# EagleIO_copy.net
KiCad netlist of a schematic drawn in EAGLE
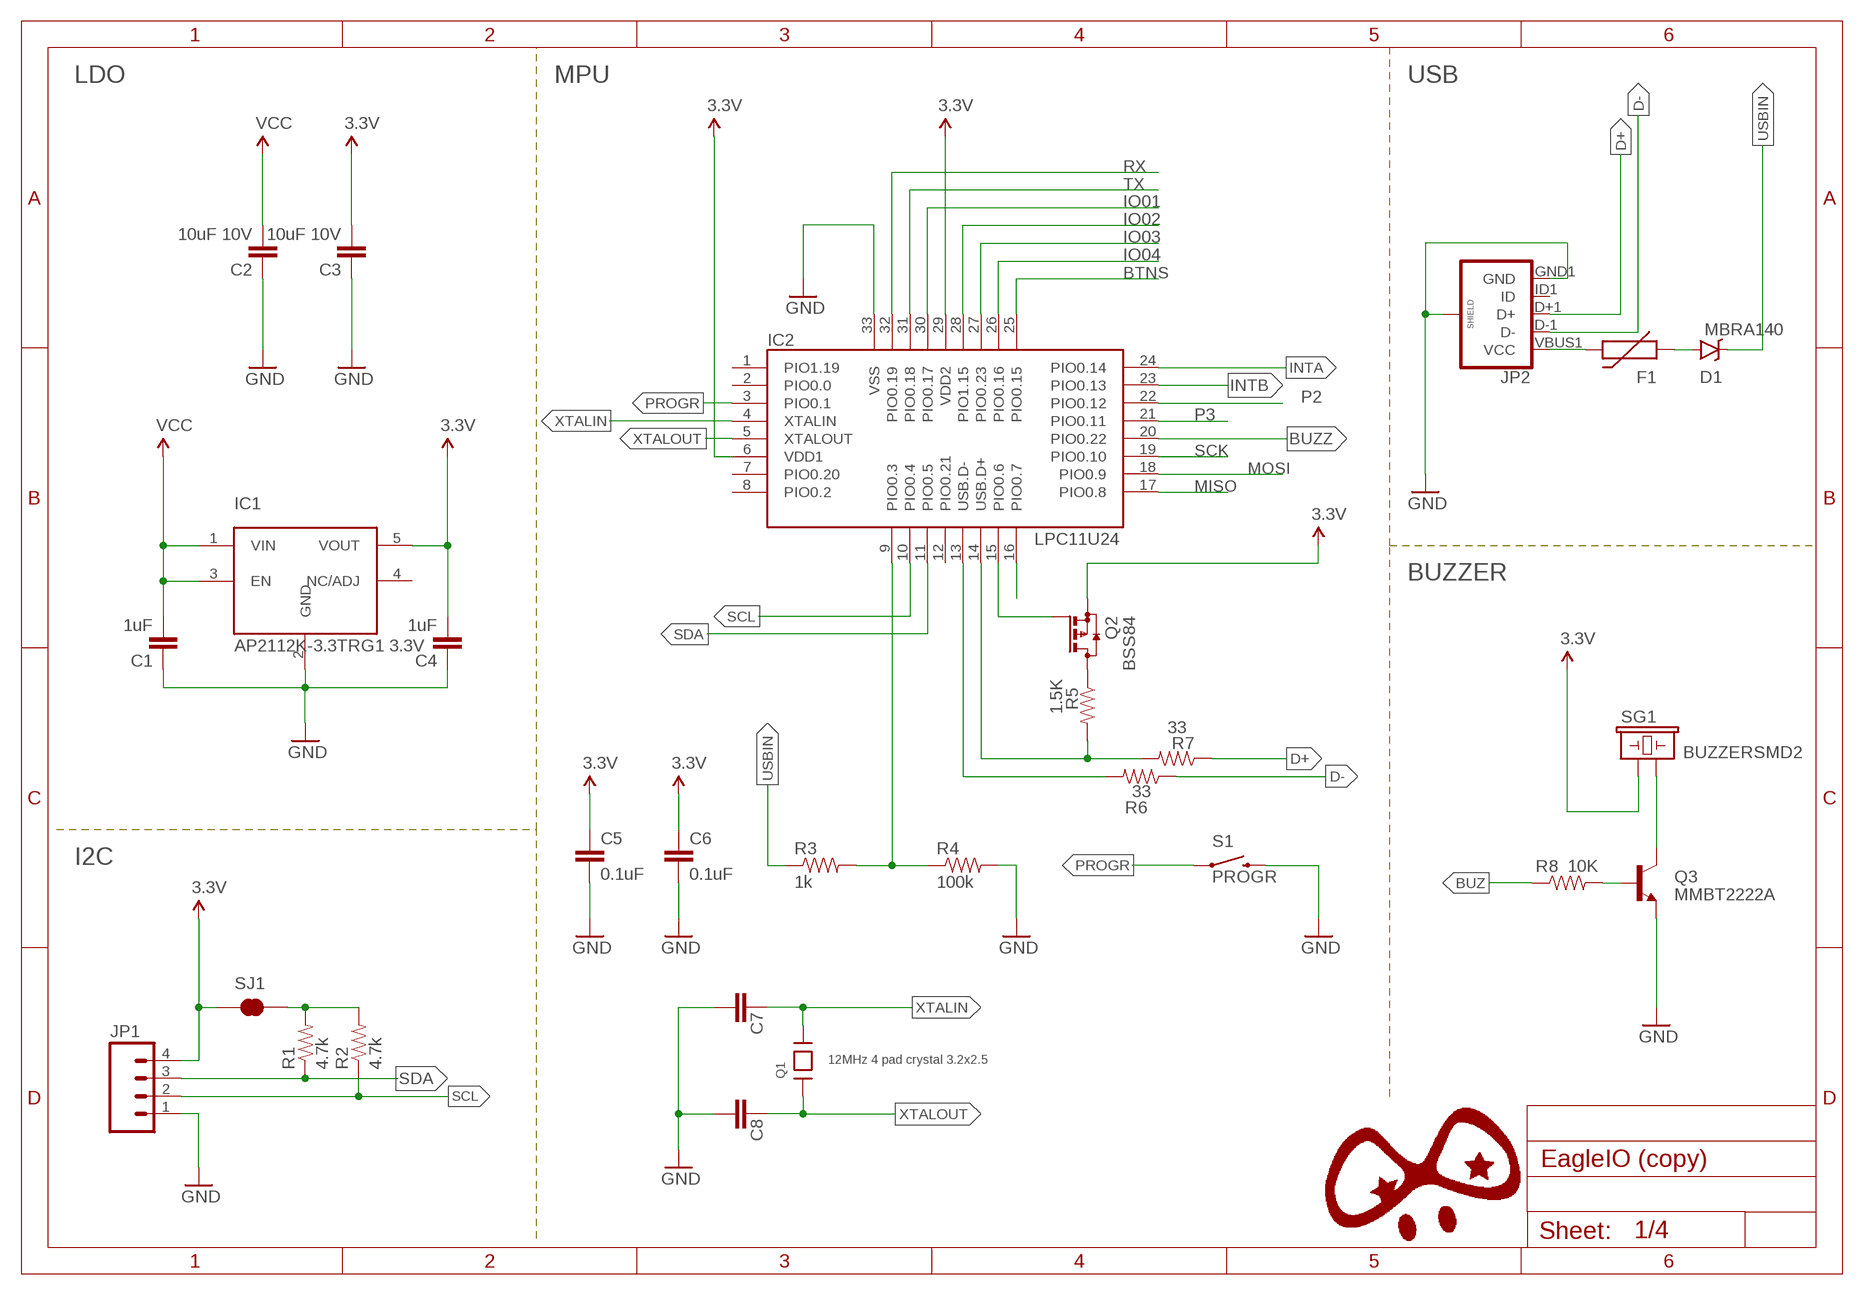
[diagram p0: schematic, sheet 1]
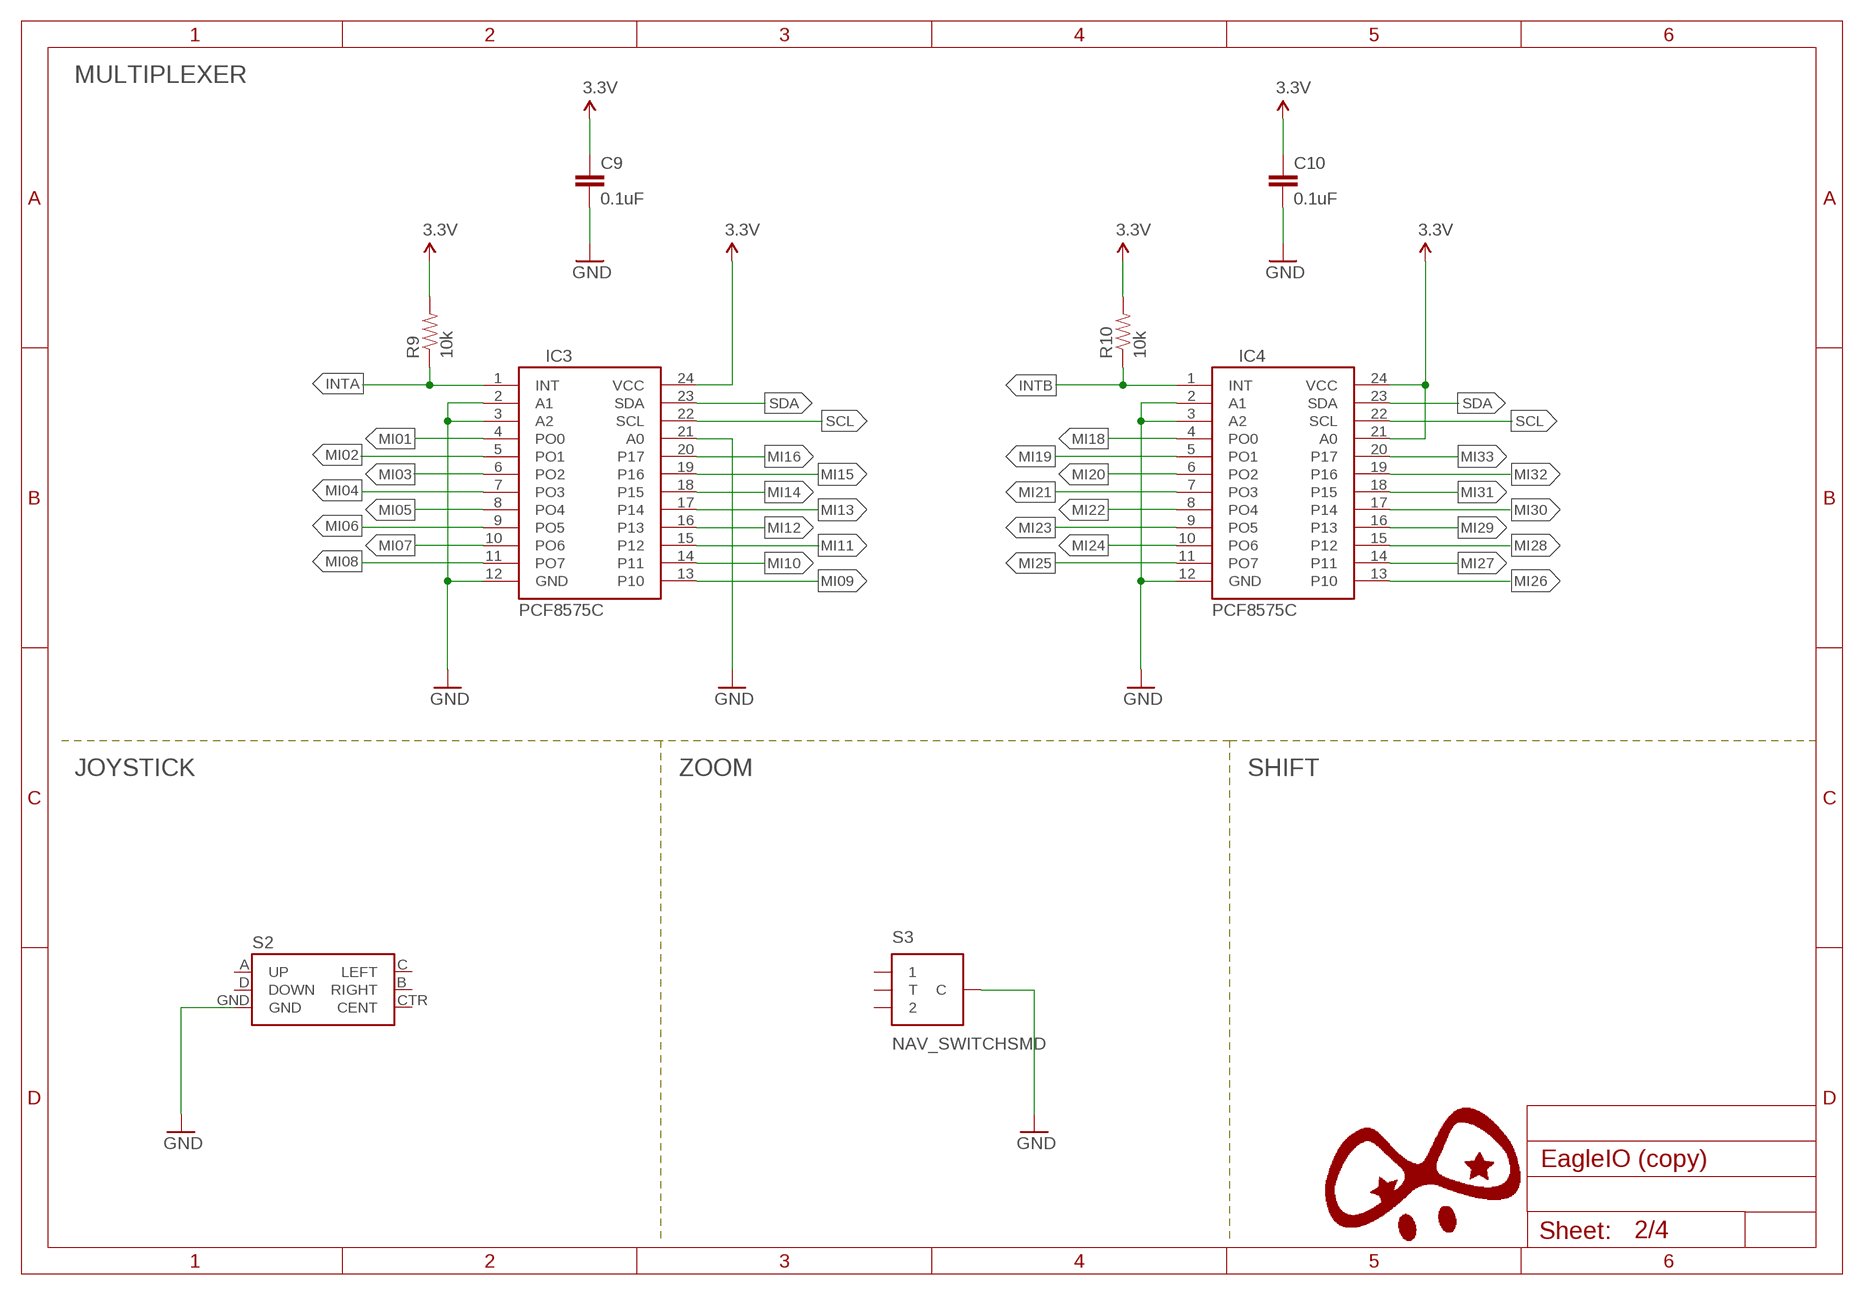
[diagram p1: schematic, sheet 2]
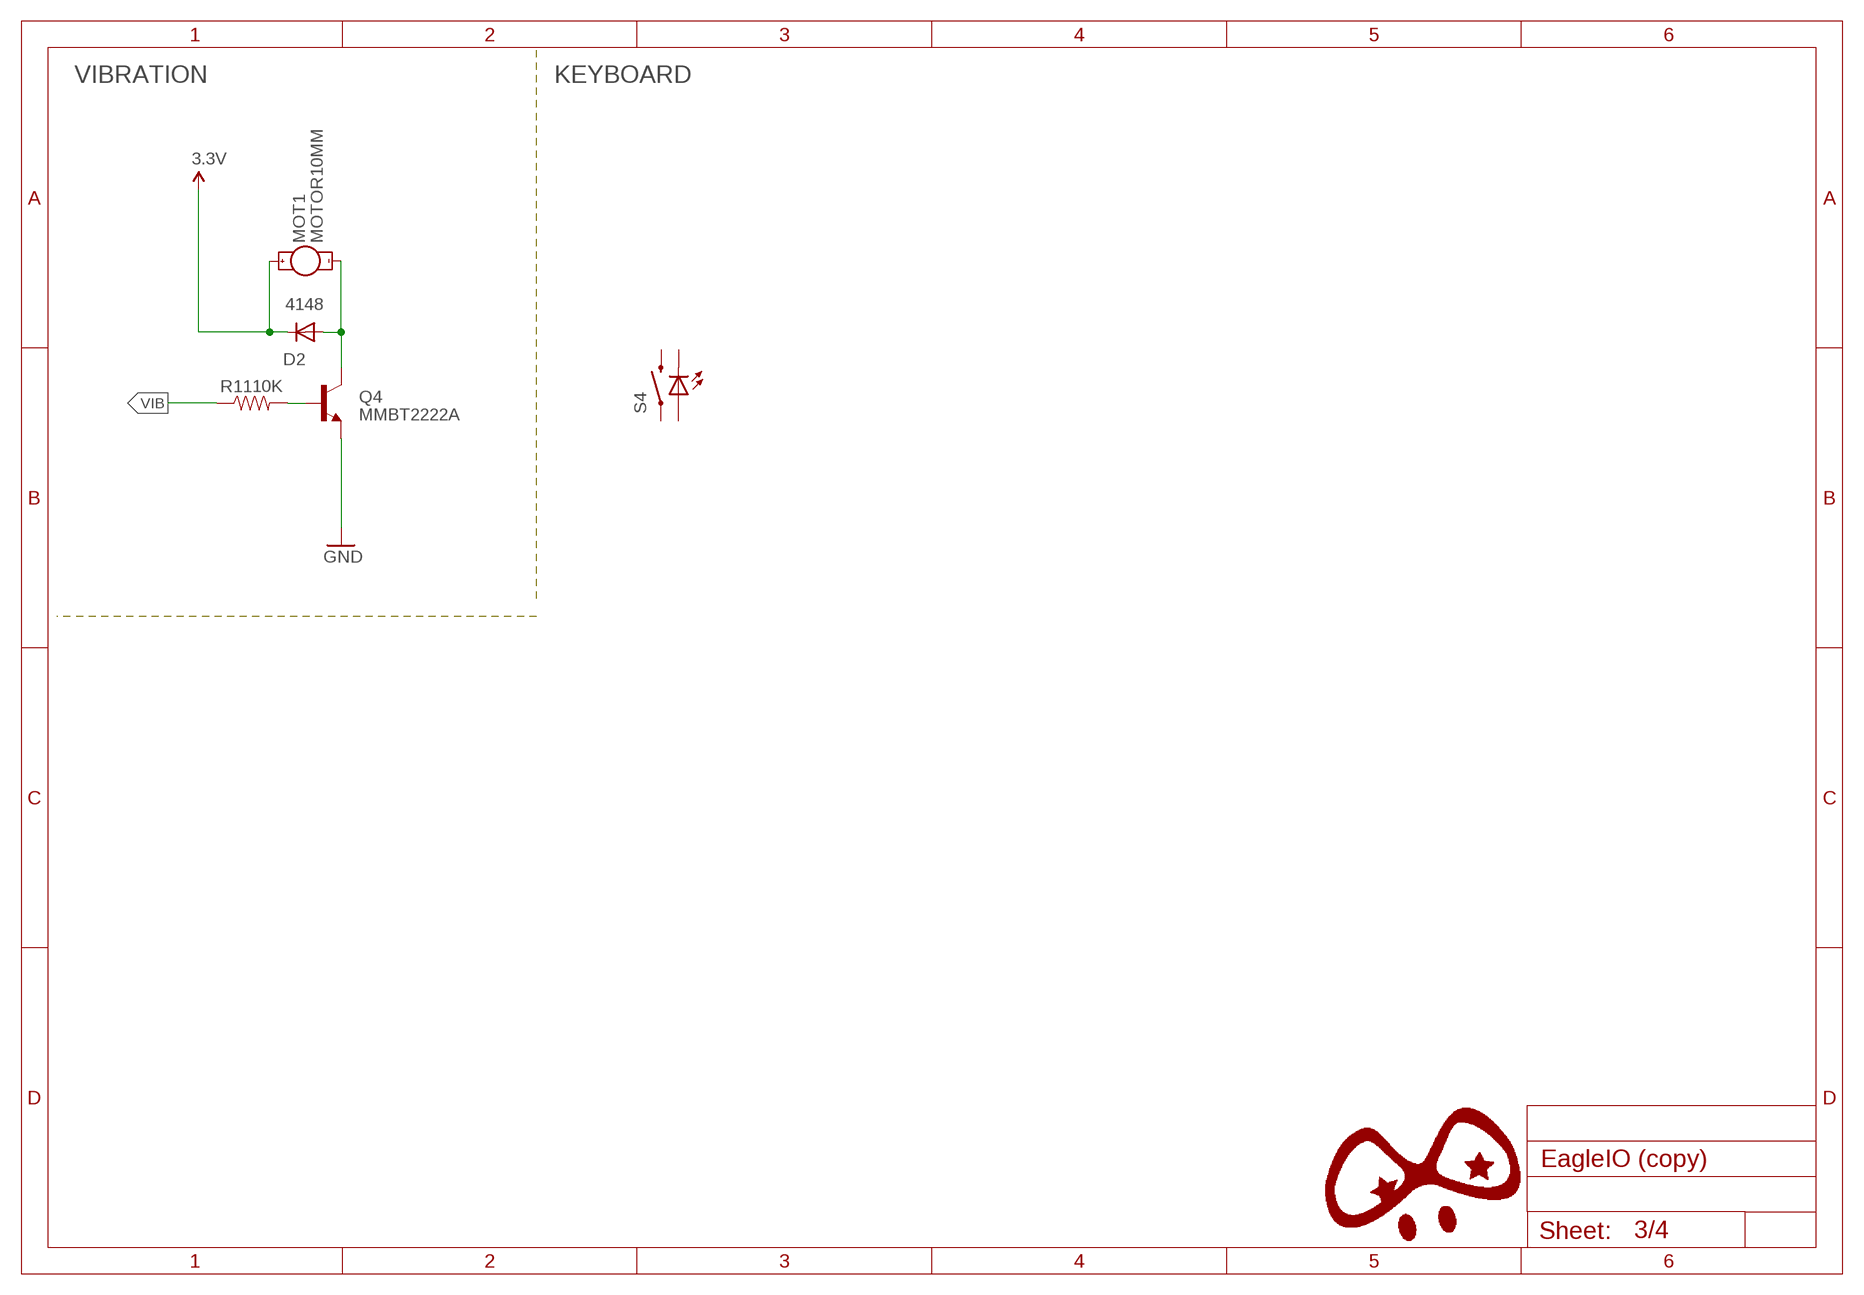
[diagram p2: schematic, sheet 3]
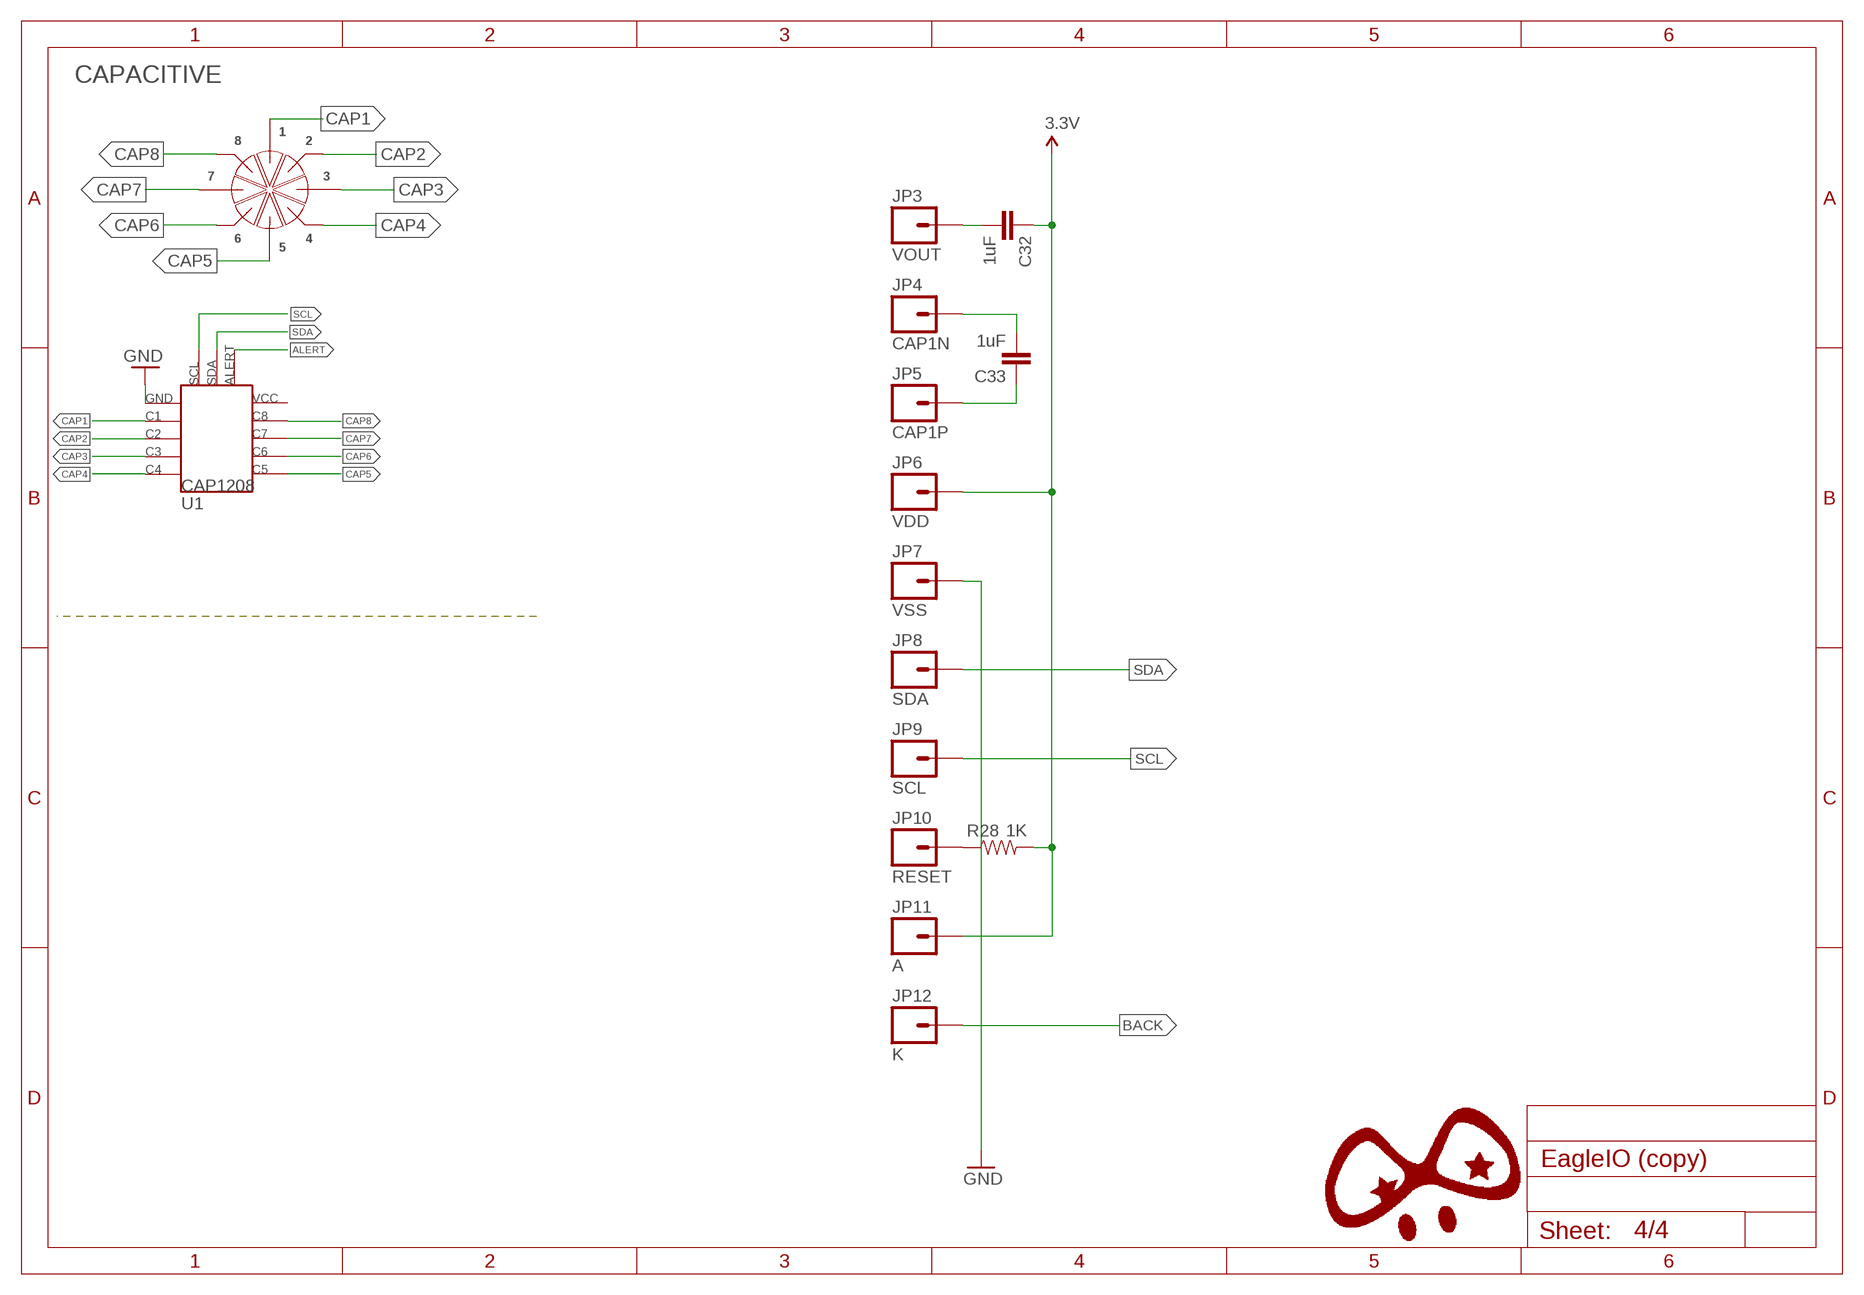
[diagram p3: schematic, sheet 4]

(export (version "E")
  (design (tool "Eeschema 10.0.6"))
  (components
    (comp (ref "C9")
      (value "0.1uF")
      (footprint "eagle-import:0402-CAP")
      (libsource (lib "eagle-import") (part "CAP0402-CAP"))
    )
    (comp (ref "C10")
      (value "0.1uF")
      (footprint "eagle-import:0402-CAP")
      (libsource (lib "eagle-import") (part "CAP0402-CAP"))
    )
    (comp (ref "IC3")
      (value "PCF8575C")
      (footprint "eagle-import:SO-24DW")
      (libsource (lib "eagle-import") (part "PCF8575C"))
    )
    (comp (ref "IC4")
      (value "PCF8575C")
      (footprint "eagle-import:SO-24DW")
      (libsource (lib "eagle-import") (part "PCF8575C"))
    )
    (comp (ref "R9")
      (value "10k")
      (footprint "eagle-import:0402-RES")
      (libsource (lib "eagle-import") (part "SparkFun-Passives_RESISTOR0402-RES"))
    )
    (comp (ref "R10")
      (value "10k")
      (footprint "eagle-import:0402-RES")
      (libsource (lib "eagle-import") (part "SparkFun-Passives_RESISTOR0402-RES"))
    )
    (comp (ref "S2")
      (value "JOYSTICK_MINI")
      (footprint "eagle-import:JOYSTICK_MINI")
      (libsource (lib "eagle-import") (part "JOYSTICK_MINI"))
    )
    (comp (ref "S3")
      (value "NAV_SWITCHSMD")
      (footprint "eagle-import:NAV_SWITCH")
      (libsource (lib "eagle-import") (part "NAV_SWITCHSMD"))
    )
    (comp (ref "C1")
      (value "1uF")
      (footprint "eagle-import:0402-CAP")
      (libsource (lib "eagle-import") (part "CAP0402-CAP"))
    )
    (comp (ref "C2")
      (value "10uF 10V")
      (footprint "eagle-import:0402-CAP")
      (libsource (lib "eagle-import") (part "CAP0402-CAP"))
    )
    (comp (ref "C3")
      (value "10uF 10V")
      (footprint "eagle-import:0402-CAP")
      (libsource (lib "eagle-import") (part "CAP0402-CAP"))
    )
    (comp (ref "C4")
      (value "1uF")
      (footprint "eagle-import:0402-CAP")
      (libsource (lib "eagle-import") (part "CAP0402-CAP"))
    )
    (comp (ref "C5")
      (value "0.1uF")
      (footprint "eagle-import:0402-CAP")
      (libsource (lib "eagle-import") (part "CAP0402-CAP"))
    )
    (comp (ref "C6")
      (value "0.1uF")
      (footprint "eagle-import:0402-CAP")
      (libsource (lib "eagle-import") (part "CAP0402-CAP"))
    )
    (comp (ref "C7")
      (value "27pF")
      (footprint "eagle-import:0402-CAP")
      (libsource (lib "eagle-import") (part "CAP0402-CAP"))
    )
    (comp (ref "C8")
      (value "27pF")
      (footprint "eagle-import:0402-CAP")
      (libsource (lib "eagle-import") (part "CAP0402-CAP"))
    )
    (comp (ref "D1")
      (value "MBRA140")
      (footprint "eagle-import:SMA-DIODE")
      (libsource (lib "eagle-import") (part "MBRA140"))
    )
    (comp (ref "F1")
      (value "PTC0603")
      (footprint "eagle-import:0603")
      (libsource (lib "eagle-import") (part "PTC0603"))
    )
    (comp (ref "IC1")
      (value "AP2112K-3.3TRG1 3.3V")
      (footprint "eagle-import:SOT23-5")
      (libsource (lib "eagle-import") (part "5PIN_REG"))
    )
    (comp (ref "IC2")
      (value "LPC11U24")
      (footprint "eagle-import:HVQFN33_5X5MM")
      (libsource (lib "eagle-import") (part "LPC11U2X_HVQFN33(5X5)"))
    )
    (comp (ref "JP1")
      (value "M04LONGPADS")
      (footprint "eagle-import:1X04_LONGPADS")
      (libsource (lib "eagle-import") (part "M04LONGPADS"))
    )
    (comp (ref "JP2")
      (value "USB_MICROB_PLUGCONN-11752")
      (footprint "eagle-import:USB-B-MICRO-SMD_V03")
      (libsource (lib "eagle-import") (part "USB_MICROB_PLUGCONN-11752"))
    )
    (comp (ref "Q1")
      (value "12MHz 4 pad crystal 3.2x2.5")
      (footprint "eagle-import:CRYSTAL_3.2X2.5")
      (libsource (lib "eagle-import") (part "CRYSTAL3.2X2.5"))
    )
    (comp (ref "Q2")
      (value "BSS84")
      (footprint "eagle-import:SOT23")
      (libsource (lib "eagle-import") (part "BSS84"))
    )
    (comp (ref "Q3")
      (value "MMBT2222A")
      (footprint "eagle-import:SOT23-3")
      (libsource (lib "eagle-import") (part "TRANSISTOR_NPNMMBT2222A"))
    )
    (comp (ref "R1")
      (value "4.7k")
      (footprint "eagle-import:0402-RES")
      (libsource (lib "eagle-import") (part "SparkFun-Passives_RESISTOR0402-RES"))
    )
    (comp (ref "R2")
      (value "4.7k")
      (footprint "eagle-import:0402-RES")
      (libsource (lib "eagle-import") (part "SparkFun-Passives_RESISTOR0402-RES"))
    )
    (comp (ref "R3")
      (value "1k")
      (footprint "eagle-import:0402-RES")
      (libsource (lib "eagle-import") (part "SparkFun-Passives_RESISTOR0402-RES"))
    )
    (comp (ref "R4")
      (value "100k")
      (footprint "eagle-import:0402-RES")
      (libsource (lib "eagle-import") (part "SparkFun-Passives_RESISTOR0402-RES"))
    )
    (comp (ref "R5")
      (value "1.5K")
      (footprint "eagle-import:0402-RES")
      (libsource (lib "eagle-import") (part "SparkFun-Passives_RESISTOR0402-RES"))
    )
    (comp (ref "R6")
      (value "33")
      (footprint "eagle-import:0402-RES")
      (libsource (lib "eagle-import") (part "SparkFun-Passives_RESISTOR0402-RES"))
    )
    (comp (ref "R7")
      (value "33")
      (footprint "eagle-import:0402-RES")
      (libsource (lib "eagle-import") (part "SparkFun-Passives_RESISTOR0402-RES"))
    )
    (comp (ref "R8")
      (value "10K")
      (footprint "eagle-import:0402-RES")
      (libsource (lib "eagle-import") (part "RESISTOR0402-RES"))
    )
    (comp (ref "S1")
      (value "PROGR")
      (footprint "eagle-import:TACTILE-SWITCH-1101NE")
      (libsource (lib "eagle-import") (part "SWITCH-MOMENTARY-2SMD-1101NE"))
    )
    (comp (ref "SG1")
      (value "BUZZERSMD2")
      (footprint "eagle-import:BUZZER-CCV")
      (libsource (lib "eagle-import") (part "BUZZERSMD2"))
    )
    (comp (ref "SJ1")
      (value "JUMPER-PAD-2-NC_BY_TRACE")
      (footprint "eagle-import:PAD-JUMPER-2-NC_BY_TRACE_YES_SILK")
      (libsource (lib "eagle-import") (part "JUMPER-PAD-2-NC_BY_TRACE"))
    )
    (comp (ref "D2")
      (value "4148")
      (footprint "eagle-import:MINIMELF")
      (libsource (lib "eagle-import") (part "DIODE-MINIMELF"))
    )
    (comp (ref "MOT1")
      (value "MOTOR10MM")
      (footprint "eagle-import:VIBE-MOTOR-10MM")
      (libsource (lib "eagle-import") (part "MOTOR10MM"))
    )
    (comp (ref "Q4")
      (value "MMBT2222A")
      (footprint "eagle-import:SOT23-3")
      (libsource (lib "eagle-import") (part "TRANSISTOR_NPNMMBT2222A"))
    )
    (comp (ref "R11")
      (value "10K")
      (footprint "eagle-import:0402-RES")
      (libsource (lib "eagle-import") (part "RESISTOR0402-RES"))
    )
    (comp (ref "S4")
      (value "SWITCH-MOMENTARY-LEDPTH")
      (footprint "eagle-import:TACTILE-PTH-LED-12MM")
      (libsource (lib "eagle-import") (part "SWITCH-MOMENTARY-LEDPTH"))
    )
    (comp (ref "C32")
      (value "1uF")
      (footprint "eagle-import:0402-CAP")
      (libsource (lib "eagle-import") (part "CAP0402-CAP"))
    )
    (comp (ref "C33")
      (value "1uF")
      (footprint "eagle-import:0402-CAP")
      (libsource (lib "eagle-import") (part "CAP0402-CAP"))
    )
    (comp (ref "JP3")
      (value "VOUT")
      (footprint "eagle-import:1X01NS-KIT")
      (libsource (lib "eagle-import") (part "M01NOSILK-KIT"))
    )
    (comp (ref "JP4")
      (value "CAP1N")
      (footprint "eagle-import:1X01NS-KIT")
      (libsource (lib "eagle-import") (part "M01NOSILK-KIT"))
    )
    (comp (ref "JP5")
      (value "CAP1P")
      (footprint "eagle-import:1X01NS-KIT")
      (libsource (lib "eagle-import") (part "M01NOSILK-KIT"))
    )
    (comp (ref "JP6")
      (value "VDD")
      (footprint "eagle-import:1X01NS-KIT")
      (libsource (lib "eagle-import") (part "M01NOSILK-KIT"))
    )
    (comp (ref "JP7")
      (value "VSS")
      (footprint "eagle-import:1X01NS-KIT")
      (libsource (lib "eagle-import") (part "M01NOSILK-KIT"))
    )
    (comp (ref "JP8")
      (value "SDA")
      (footprint "eagle-import:1X01NS-KIT")
      (libsource (lib "eagle-import") (part "M01NOSILK-KIT"))
    )
    (comp (ref "JP9")
      (value "SCL")
      (footprint "eagle-import:1X01NS-KIT")
      (libsource (lib "eagle-import") (part "M01NOSILK-KIT"))
    )
    (comp (ref "JP10")
      (value "RESET")
      (footprint "eagle-import:1X01NS-KIT")
      (libsource (lib "eagle-import") (part "M01NOSILK-KIT"))
    )
    (comp (ref "JP11")
      (value "A")
      (footprint "eagle-import:1X01NS-KIT")
      (libsource (lib "eagle-import") (part "M01NOSILK-KIT"))
    )
    (comp (ref "JP12")
      (value "K")
      (footprint "eagle-import:1X01NS-KIT")
      (libsource (lib "eagle-import") (part "M01NOSILK-KIT"))
    )
    (comp (ref "R28")
      (value "1K")
      (footprint "eagle-import:0402-RES")
      (libsource (lib "eagle-import") (part "RESISTOR0402-RES"))
    )
    (comp (ref "U1")
      (value "CAP1208")
      (footprint "eagle-import:QFN_16")
      (libsource (lib "eagle-import") (part "CAP1208"))
    )
    (comp (ref "W1")
      (value "CAP_WHEEL")
      (footprint "eagle-import:CAP_WHEEL")
      (libsource (lib "eagle-import") (part "CAP_WHEEL"))
    )
  )
  (nets
    (net (code "1") (name "3.3V") (class "Default")
      (node (ref "C10") (pin "1") (pinfunction "1_1") (pintype "passive"))
      (node (ref "C3") (pin "2") (pinfunction "2_2") (pintype "passive"))
      (node (ref "C32") (pin "1") (pinfunction "1_1") (pintype "passive"))
      (node (ref "C4") (pin "2") (pinfunction "2_2") (pintype "passive"))
      (node (ref "C5") (pin "1") (pinfunction "1_1") (pintype "passive"))
      (node (ref "C6") (pin "1") (pinfunction "1_1") (pintype "passive"))
      (node (ref "C9") (pin "1") (pinfunction "1_1") (pintype "passive"))
      (node (ref "D2") (pin "C") (pinfunction "C_C") (pintype "passive"))
      (node (ref "IC1") (pin "5") (pinfunction "VOUT_5") (pintype "bidirectional"))
      (node (ref "IC2") (pin "29") (pinfunction "VDD2_29") (pintype "bidirectional"))
      (node (ref "IC2") (pin "6") (pinfunction "VDD1_6") (pintype "bidirectional"))
      (node (ref "IC3") (pin "24") (pinfunction "VCC_24") (pintype "bidirectional"))
      (node (ref "IC4") (pin "21") (pinfunction "A0_21") (pintype "bidirectional"))
      (node (ref "IC4") (pin "24") (pinfunction "VCC_24") (pintype "bidirectional"))
      (node (ref "JP1") (pin "4") (pinfunction "4_4") (pintype "passive"))
      (node (ref "JP11") (pin "1") (pinfunction "1_1") (pintype "passive"))
      (node (ref "JP6") (pin "1") (pinfunction "1_1") (pintype "passive"))
      (node (ref "MOT1") (pin "+") (pinfunction "+_+") (pintype "bidirectional"))
      (node (ref "Q2") (pin "2") (pinfunction "S_2") (pintype "passive"))
      (node (ref "R10") (pin "2") (pinfunction "2_2") (pintype "passive"))
      (node (ref "R28") (pin "2") (pinfunction "2_2") (pintype "passive"))
      (node (ref "R9") (pin "2") (pinfunction "2_2") (pintype "passive"))
      (node (ref "SG1") (pin "+") (pinfunction "1_+") (pintype "passive"))
      (node (ref "SJ1") (pin "1") (pinfunction "1_1") (pintype "passive"))
    )
    (net (code "2") (name "ALERT") (class "Default")
      (node (ref "U1") (pin "1") (pinfunction "ALERT_1") (pintype "bidirectional"))
    )
    (net (code "3") (name "BACK") (class "Default")
      (node (ref "JP12") (pin "1") (pinfunction "1_1") (pintype "passive"))
    )
    (net (code "4") (name "BTNS") (class "Default")
      (node (ref "IC2") (pin "25") (pinfunction "PIO0.15_25") (pintype "bidirectional"))
    )
    (net (code "5") (name "BUZ") (class "Default")
      (node (ref "R8") (pin "1") (pinfunction "1_1") (pintype "passive"))
    )
    (net (code "6") (name "BUZZ") (class "Default")
      (node (ref "IC2") (pin "20") (pinfunction "PIO0.22_20") (pintype "bidirectional"))
    )
    (net (code "7") (name "CAP1") (class "Default")
      (node (ref "U1") (pin "16") (pinfunction "C1_16") (pintype "bidirectional"))
      (node (ref "W1") (pin "1") (pinfunction "1_1") (pintype "bidirectional"))
    )
    (net (code "8") (name "CAP2") (class "Default")
      (node (ref "U1") (pin "15") (pinfunction "C2_15") (pintype "bidirectional"))
      (node (ref "W1") (pin "2") (pinfunction "2_2") (pintype "bidirectional"))
    )
    (net (code "9") (name "CAP3") (class "Default")
      (node (ref "U1") (pin "14") (pinfunction "C3_14") (pintype "bidirectional"))
      (node (ref "W1") (pin "3") (pinfunction "3_3") (pintype "bidirectional"))
    )
    (net (code "10") (name "CAP4") (class "Default")
      (node (ref "U1") (pin "13") (pinfunction "C4_13") (pintype "bidirectional"))
      (node (ref "W1") (pin "4") (pinfunction "4_4") (pintype "bidirectional"))
    )
    (net (code "11") (name "CAP5") (class "Default")
      (node (ref "U1") (pin "12") (pinfunction "C5_12") (pintype "bidirectional"))
      (node (ref "W1") (pin "5") (pinfunction "5_5") (pintype "bidirectional"))
    )
    (net (code "12") (name "CAP6") (class "Default")
      (node (ref "U1") (pin "11") (pinfunction "C6_11") (pintype "bidirectional"))
      (node (ref "W1") (pin "6") (pinfunction "6_6") (pintype "bidirectional"))
    )
    (net (code "13") (name "CAP7") (class "Default")
      (node (ref "U1") (pin "10") (pinfunction "C7_10") (pintype "bidirectional"))
      (node (ref "W1") (pin "7") (pinfunction "7_7") (pintype "bidirectional"))
    )
    (net (code "14") (name "CAP8") (class "Default")
      (node (ref "U1") (pin "9") (pinfunction "C8_9") (pintype "bidirectional"))
      (node (ref "W1") (pin "8") (pinfunction "8_8") (pintype "bidirectional"))
    )
    (net (code "15") (name "D+") (class "Default")
      (node (ref "JP2") (pin "D+1") (pinfunction "D+_D+1") (pintype "bidirectional"))
      (node (ref "R7") (pin "1") (pinfunction "1_1") (pintype "passive"))
    )
    (net (code "16") (name "D-") (class "Default")
      (node (ref "JP2") (pin "D-1") (pinfunction "D-_D-1") (pintype "bidirectional"))
      (node (ref "R6") (pin "1") (pinfunction "1_1") (pintype "passive"))
    )
    (net (code "17") (name "GND") (class "Default")
      (node (ref "C1") (pin "1") (pinfunction "1_1") (pintype "passive"))
      (node (ref "C10") (pin "2") (pinfunction "2_2") (pintype "passive"))
      (node (ref "C2") (pin "1") (pinfunction "1_1") (pintype "passive"))
      (node (ref "C3") (pin "1") (pinfunction "1_1") (pintype "passive"))
      (node (ref "C4") (pin "1") (pinfunction "1_1") (pintype "passive"))
      (node (ref "C5") (pin "2") (pinfunction "2_2") (pintype "passive"))
      (node (ref "C6") (pin "2") (pinfunction "2_2") (pintype "passive"))
      (node (ref "C7") (pin "2") (pinfunction "2_2") (pintype "passive"))
      (node (ref "C8") (pin "2") (pinfunction "2_2") (pintype "passive"))
      (node (ref "C9") (pin "2") (pinfunction "2_2") (pintype "passive"))
      (node (ref "IC1") (pin "2") (pinfunction "GND_2") (pintype "bidirectional"))
      (node (ref "IC2") (pin "33") (pinfunction "VSS_33") (pintype "bidirectional"))
      (node (ref "IC3") (pin "12") (pinfunction "GND_12") (pintype "bidirectional"))
      (node (ref "IC3") (pin "2") (pinfunction "A1_2") (pintype "bidirectional"))
      (node (ref "IC3") (pin "21") (pinfunction "A0_21") (pintype "bidirectional"))
      (node (ref "IC3") (pin "3") (pinfunction "A2_3") (pintype "bidirectional"))
      (node (ref "IC4") (pin "12") (pinfunction "GND_12") (pintype "bidirectional"))
      (node (ref "IC4") (pin "2") (pinfunction "A1_2") (pintype "bidirectional"))
      (node (ref "IC4") (pin "3") (pinfunction "A2_3") (pintype "bidirectional"))
      (node (ref "JP1") (pin "1") (pinfunction "1_1") (pintype "passive"))
      (node (ref "JP2") (pin "GND1") (pinfunction "GND_GND1") (pintype "bidirectional"))
      (node (ref "JP2") (pin "SHIELD1") (pinfunction "SHIELD_SHIELD1") (pintype "bidirectional"))
      (node (ref "JP2") (pin "SHIELD2") (pinfunction "SHIELD_SHIELD2") (pintype "bidirectional"))
      (node (ref "JP2") (pin "SHIELD3") (pinfunction "SHIELD_SHIELD3") (pintype "bidirectional"))
      (node (ref "JP7") (pin "1") (pinfunction "1_1") (pintype "passive"))
      (node (ref "Q3") (pin "2") (pinfunction "E_2") (pintype "passive"))
      (node (ref "Q4") (pin "2") (pinfunction "E_2") (pintype "passive"))
      (node (ref "R4") (pin "2") (pinfunction "2_2") (pintype "passive"))
      (node (ref "S1") (pin "2") (pinfunction "2_2") (pintype "passive"))
      (node (ref "S2") (pin "GND") (pinfunction "GND_GND") (pintype "bidirectional"))
      (node (ref "S3") (pin "C") (pinfunction "C_C") (pintype "power_in"))
      (node (ref "U1") (pin "7") (pinfunction "GND_7") (pintype "bidirectional"))
      (node (ref "U1") (pin "8") (pinfunction "GND_8") (pintype "bidirectional"))
      (node (ref "U1") (pin "EXT") (pinfunction "GND_EXT") (pintype "bidirectional"))
    )
    (net (code "18") (name "INTA") (class "Default")
      (node (ref "IC2") (pin "24") (pinfunction "PIO0.14_24") (pintype "bidirectional"))
      (node (ref "IC3") (pin "1") (pinfunction "INT_1") (pintype "bidirectional"))
      (node (ref "R9") (pin "1") (pinfunction "1_1") (pintype "passive"))
    )
    (net (code "19") (name "INTB") (class "Default")
      (node (ref "IC2") (pin "23") (pinfunction "PIO0.13_23") (pintype "bidirectional"))
      (node (ref "IC4") (pin "1") (pinfunction "INT_1") (pintype "bidirectional"))
      (node (ref "R10") (pin "1") (pinfunction "1_1") (pintype "passive"))
    )
    (net (code "20") (name "IO01") (class "Default")
      (node (ref "IC2") (pin "30") (pinfunction "PIO0.17_30") (pintype "bidirectional"))
    )
    (net (code "21") (name "IO02") (class "Default")
      (node (ref "IC2") (pin "28") (pinfunction "PIO1.15_28") (pintype "bidirectional"))
    )
    (net (code "22") (name "IO03") (class "Default")
      (node (ref "IC2") (pin "27") (pinfunction "PIO0.23_27") (pintype "bidirectional"))
    )
    (net (code "23") (name "IO04") (class "Default")
      (node (ref "IC2") (pin "26") (pinfunction "PIO0.16_26") (pintype "bidirectional"))
    )
    (net (code "24") (name "MI01") (class "Default")
      (node (ref "IC3") (pin "4") (pinfunction "PO0_4") (pintype "bidirectional"))
    )
    (net (code "25") (name "MI02") (class "Default")
      (node (ref "IC3") (pin "5") (pinfunction "PO1_5") (pintype "bidirectional"))
    )
    (net (code "26") (name "MI03") (class "Default")
      (node (ref "IC3") (pin "6") (pinfunction "PO2_6") (pintype "bidirectional"))
    )
    (net (code "27") (name "MI04") (class "Default")
      (node (ref "IC3") (pin "7") (pinfunction "PO3_7") (pintype "bidirectional"))
    )
    (net (code "28") (name "MI05") (class "Default")
      (node (ref "IC3") (pin "8") (pinfunction "PO4_8") (pintype "bidirectional"))
    )
    (net (code "29") (name "MI06") (class "Default")
      (node (ref "IC3") (pin "9") (pinfunction "PO5_9") (pintype "bidirectional"))
    )
    (net (code "30") (name "MI07") (class "Default")
      (node (ref "IC3") (pin "10") (pinfunction "PO6_10") (pintype "bidirectional"))
    )
    (net (code "31") (name "MI08") (class "Default")
      (node (ref "IC3") (pin "11") (pinfunction "PO7_11") (pintype "bidirectional"))
    )
    (net (code "32") (name "MI09") (class "Default")
      (node (ref "IC3") (pin "13") (pinfunction "P10_13") (pintype "bidirectional"))
    )
    (net (code "33") (name "MI10") (class "Default")
      (node (ref "IC3") (pin "14") (pinfunction "P11_14") (pintype "bidirectional"))
    )
    (net (code "34") (name "MI11") (class "Default")
      (node (ref "IC3") (pin "15") (pinfunction "P12_15") (pintype "bidirectional"))
    )
    (net (code "35") (name "MI12") (class "Default")
      (node (ref "IC3") (pin "16") (pinfunction "P13_16") (pintype "bidirectional"))
    )
    (net (code "36") (name "MI13") (class "Default")
      (node (ref "IC3") (pin "17") (pinfunction "P14_17") (pintype "bidirectional"))
    )
    (net (code "37") (name "MI14") (class "Default")
      (node (ref "IC3") (pin "18") (pinfunction "P15_18") (pintype "bidirectional"))
    )
    (net (code "38") (name "MI15") (class "Default")
      (node (ref "IC3") (pin "19") (pinfunction "P16_19") (pintype "bidirectional"))
    )
    (net (code "39") (name "MI16") (class "Default")
      (node (ref "IC3") (pin "20") (pinfunction "P17_20") (pintype "bidirectional"))
    )
    (net (code "40") (name "MI18") (class "Default")
      (node (ref "IC4") (pin "4") (pinfunction "PO0_4") (pintype "bidirectional"))
    )
    (net (code "41") (name "MI19") (class "Default")
      (node (ref "IC4") (pin "5") (pinfunction "PO1_5") (pintype "bidirectional"))
    )
    (net (code "42") (name "MI20") (class "Default")
      (node (ref "IC4") (pin "6") (pinfunction "PO2_6") (pintype "bidirectional"))
    )
    (net (code "43") (name "MI21") (class "Default")
      (node (ref "IC4") (pin "7") (pinfunction "PO3_7") (pintype "bidirectional"))
    )
    (net (code "44") (name "MI22") (class "Default")
      (node (ref "IC4") (pin "8") (pinfunction "PO4_8") (pintype "bidirectional"))
    )
    (net (code "45") (name "MI23") (class "Default")
      (node (ref "IC4") (pin "9") (pinfunction "PO5_9") (pintype "bidirectional"))
    )
    (net (code "46") (name "MI24") (class "Default")
      (node (ref "IC4") (pin "10") (pinfunction "PO6_10") (pintype "bidirectional"))
    )
    (net (code "47") (name "MI25") (class "Default")
      (node (ref "IC4") (pin "11") (pinfunction "PO7_11") (pintype "bidirectional"))
    )
    (net (code "48") (name "MI26") (class "Default")
      (node (ref "IC4") (pin "13") (pinfunction "P10_13") (pintype "bidirectional"))
    )
    (net (code "49") (name "MI27") (class "Default")
      (node (ref "IC4") (pin "14") (pinfunction "P11_14") (pintype "bidirectional"))
    )
    (net (code "50") (name "MI28") (class "Default")
      (node (ref "IC4") (pin "15") (pinfunction "P12_15") (pintype "bidirectional"))
    )
    (net (code "51") (name "MI29") (class "Default")
      (node (ref "IC4") (pin "16") (pinfunction "P13_16") (pintype "bidirectional"))
    )
    (net (code "52") (name "MI30") (class "Default")
      (node (ref "IC4") (pin "17") (pinfunction "P14_17") (pintype "bidirectional"))
    )
    (net (code "53") (name "MI31") (class "Default")
      (node (ref "IC4") (pin "18") (pinfunction "P15_18") (pintype "bidirectional"))
    )
    (net (code "54") (name "MI32") (class "Default")
      (node (ref "IC4") (pin "19") (pinfunction "P16_19") (pintype "bidirectional"))
    )
    (net (code "55") (name "MI33") (class "Default")
      (node (ref "IC4") (pin "20") (pinfunction "P17_20") (pintype "bidirectional"))
    )
    (net (code "56") (name "MISO") (class "Default")
      (node (ref "IC2") (pin "17") (pinfunction "PIO0.8_17") (pintype "bidirectional"))
    )
    (net (code "57") (name "MOSI") (class "Default")
      (node (ref "IC2") (pin "18") (pinfunction "PIO0.9_18") (pintype "bidirectional"))
    )
    (net (code "58") (name "Net-(C32-Pad2)") (class "Default")
      (node (ref "C32") (pin "2") (pinfunction "2_2") (pintype "passive"))
      (node (ref "JP3") (pin "1") (pinfunction "1_1") (pintype "passive"))
    )
    (net (code "59") (name "Net-(C33-Pad1)") (class "Default")
      (node (ref "C33") (pin "1") (pinfunction "1_1") (pintype "passive"))
      (node (ref "JP5") (pin "1") (pinfunction "1_1") (pintype "passive"))
    )
    (net (code "60") (name "Net-(C33-Pad2)") (class "Default")
      (node (ref "C33") (pin "2") (pinfunction "2_2") (pintype "passive"))
      (node (ref "JP4") (pin "1") (pinfunction "1_1") (pintype "passive"))
    )
    (net (code "61") (name "Net-(D1-PadA)") (class "Default")
      (node (ref "D1") (pin "A") (pinfunction "A_A") (pintype "passive"))
      (node (ref "F1") (pin "1") (pinfunction "1_1") (pintype "bidirectional"))
    )
    (net (code "62") (name "Net-(IC2-PIO0.3)") (class "Default")
      (node (ref "IC2") (pin "9") (pinfunction "PIO0.3_9") (pintype "bidirectional"))
      (node (ref "R3") (pin "2") (pinfunction "2_2") (pintype "passive"))
      (node (ref "R4") (pin "1") (pinfunction "1_1") (pintype "passive"))
    )
    (net (code "63") (name "Net-(IC2-PIO0.6)") (class "Default")
      (node (ref "IC2") (pin "15") (pinfunction "PIO0.6_15") (pintype "bidirectional"))
      (node (ref "Q2") (pin "1") (pinfunction "G_1") (pintype "passive"))
    )
    (net (code "64") (name "Net-(IC2-USB.D+)") (class "Default")
      (node (ref "IC2") (pin "14") (pinfunction "USB.D+_14") (pintype "bidirectional"))
      (node (ref "R5") (pin "2") (pinfunction "2_2") (pintype "passive"))
      (node (ref "R7") (pin "2") (pinfunction "2_2") (pintype "passive"))
    )
    (net (code "65") (name "Net-(IC2-USB.D-)") (class "Default")
      (node (ref "IC2") (pin "13") (pinfunction "USB.D-_13") (pintype "bidirectional"))
      (node (ref "R6") (pin "2") (pinfunction "2_2") (pintype "passive"))
    )
    (net (code "66") (name "Net-(JP2-VCC)") (class "Default")
      (node (ref "F1") (pin "2") (pinfunction "2_2") (pintype "bidirectional"))
      (node (ref "JP2") (pin "VBUS1") (pinfunction "VCC_VBUS1") (pintype "bidirectional"))
    )
    (net (code "67") (name "Net-(JP10-Pad1)") (class "Default")
      (node (ref "JP10") (pin "1") (pinfunction "1_1") (pintype "passive"))
      (node (ref "R28") (pin "1") (pinfunction "1_1") (pintype "passive"))
    )
    (net (code "68") (name "Net-(Q2-D)") (class "Default")
      (node (ref "Q2") (pin "3") (pinfunction "D_3") (pintype "passive"))
      (node (ref "R5") (pin "1") (pinfunction "1_1") (pintype "passive"))
    )
    (net (code "69") (name "Net-(Q3-B)") (class "Default")
      (node (ref "Q3") (pin "1") (pinfunction "B_1") (pintype "passive"))
      (node (ref "R8") (pin "2") (pinfunction "2_2") (pintype "passive"))
    )
    (net (code "70") (name "Net-(Q3-C)") (class "Default")
      (node (ref "Q3") (pin "3") (pinfunction "C_3") (pintype "passive"))
      (node (ref "SG1") (pin "-") (pinfunction "2_-") (pintype "passive"))
    )
    (net (code "71") (name "Net-(Q4-B)") (class "Default")
      (node (ref "Q4") (pin "1") (pinfunction "B_1") (pintype "passive"))
      (node (ref "R11") (pin "2") (pinfunction "2_2") (pintype "passive"))
    )
    (net (code "72") (name "Net-(Q4-C)") (class "Default")
      (node (ref "D2") (pin "A") (pinfunction "A_A") (pintype "passive"))
      (node (ref "MOT1") (pin "-") (pinfunction "-_-") (pintype "bidirectional"))
      (node (ref "Q4") (pin "3") (pinfunction "C_3") (pintype "passive"))
    )
    (net (code "73") (name "Net-(R1-Pad2)") (class "Default")
      (node (ref "R1") (pin "2") (pinfunction "2_2") (pintype "passive"))
      (node (ref "R2") (pin "2") (pinfunction "2_2") (pintype "passive"))
      (node (ref "SJ1") (pin "2") (pinfunction "2_2") (pintype "passive"))
    )
    (net (code "74") (name "P2") (class "Default")
      (node (ref "IC2") (pin "22") (pinfunction "PIO0.12_22") (pintype "bidirectional"))
    )
    (net (code "75") (name "P3") (class "Default")
      (node (ref "IC2") (pin "21") (pinfunction "PIO0.11_21") (pintype "bidirectional"))
    )
    (net (code "76") (name "PROGR") (class "Default")
      (node (ref "IC2") (pin "3") (pinfunction "PIO0.1_3") (pintype "bidirectional"))
      (node (ref "S1") (pin "1") (pinfunction "1_1") (pintype "passive"))
    )
    (net (code "77") (name "RX") (class "Default")
      (node (ref "IC2") (pin "32") (pinfunction "PIO0.19_32") (pintype "bidirectional"))
    )
    (net (code "78") (name "SCK") (class "Default")
      (node (ref "IC2") (pin "19") (pinfunction "PIO0.10_19") (pintype "bidirectional"))
    )
    (net (code "79") (name "SCL") (class "Default")
      (node (ref "IC2") (pin "10") (pinfunction "PIO0.4_10") (pintype "bidirectional"))
      (node (ref "IC3") (pin "22") (pinfunction "SCL_22") (pintype "bidirectional"))
      (node (ref "IC4") (pin "22") (pinfunction "SCL_22") (pintype "bidirectional"))
      (node (ref "JP1") (pin "2") (pinfunction "2_2") (pintype "passive"))
      (node (ref "JP9") (pin "1") (pinfunction "1_1") (pintype "passive"))
      (node (ref "R2") (pin "1") (pinfunction "1_1") (pintype "passive"))
      (node (ref "U1") (pin "3") (pinfunction "SCL_3") (pintype "bidirectional"))
    )
    (net (code "80") (name "SDA") (class "Default")
      (node (ref "IC2") (pin "11") (pinfunction "PIO0.5_11") (pintype "bidirectional"))
      (node (ref "IC3") (pin "23") (pinfunction "SDA_23") (pintype "bidirectional"))
      (node (ref "IC4") (pin "23") (pinfunction "SDA_23") (pintype "bidirectional"))
      (node (ref "JP1") (pin "3") (pinfunction "3_3") (pintype "passive"))
      (node (ref "JP8") (pin "1") (pinfunction "1_1") (pintype "passive"))
      (node (ref "R1") (pin "1") (pinfunction "1_1") (pintype "passive"))
      (node (ref "U1") (pin "2") (pinfunction "SDA_2") (pintype "bidirectional"))
    )
    (net (code "81") (name "TX") (class "Default")
      (node (ref "IC2") (pin "31") (pinfunction "PIO0.18_31") (pintype "bidirectional"))
    )
    (net (code "82") (name "USBIN") (class "Default")
      (node (ref "D1") (pin "C") (pinfunction "C_C") (pintype "passive"))
      (node (ref "R3") (pin "1") (pinfunction "1_1") (pintype "passive"))
    )
    (net (code "83") (name "VCC") (class "Default")
      (node (ref "C1") (pin "2") (pinfunction "2_2") (pintype "passive"))
      (node (ref "C2") (pin "2") (pinfunction "2_2") (pintype "passive"))
      (node (ref "IC1") (pin "1") (pinfunction "VIN_1") (pintype "bidirectional"))
      (node (ref "IC1") (pin "3") (pinfunction "EN_3") (pintype "bidirectional"))
    )
    (net (code "84") (name "VIB") (class "Default")
      (node (ref "R11") (pin "1") (pinfunction "1_1") (pintype "passive"))
    )
    (net (code "85") (name "XTALIN") (class "Default")
      (node (ref "C7") (pin "1") (pinfunction "1_1") (pintype "passive"))
      (node (ref "IC2") (pin "4") (pinfunction "XTALIN_4") (pintype "bidirectional"))
      (node (ref "Q1") (pin "3") (pinfunction "P$2_3") (pintype "passive"))
    )
    (net (code "86") (name "XTALOUT") (class "Default")
      (node (ref "C8") (pin "1") (pinfunction "1_1") (pintype "passive"))
      (node (ref "IC2") (pin "5") (pinfunction "XTALOUT_5") (pintype "bidirectional"))
      (node (ref "Q1") (pin "1") (pinfunction "P$1_1") (pintype "passive"))
    )
    (net (code "87") (name "unconnected-(IC1-NC{slash}ADJ-Pad4)") (class "Default")
      (node (ref "IC1") (pin "4") (pinfunction "NC/ADJ_4") (pintype "bidirectional"))
    )
    (net (code "88") (name "unconnected-(IC2-PIO0.0-Pad2)") (class "Default")
      (node (ref "IC2") (pin "2") (pinfunction "PIO0.0_2") (pintype "bidirectional"))
    )
    (net (code "89") (name "unconnected-(IC2-PIO0.2-Pad8)") (class "Default")
      (node (ref "IC2") (pin "8") (pinfunction "PIO0.2_8") (pintype "bidirectional"))
    )
    (net (code "90") (name "unconnected-(IC2-PIO0.7-Pad16)") (class "Default")
      (node (ref "IC2") (pin "16") (pinfunction "PIO0.7_16") (pintype "bidirectional"))
    )
    (net (code "91") (name "unconnected-(IC2-PIO0.20-Pad7)") (class "Default")
      (node (ref "IC2") (pin "7") (pinfunction "PIO0.20_7") (pintype "bidirectional"))
    )
    (net (code "92") (name "unconnected-(IC2-PIO0.21-Pad12)") (class "Default")
      (node (ref "IC2") (pin "12") (pinfunction "PIO0.21_12") (pintype "bidirectional"))
    )
    (net (code "93") (name "unconnected-(IC2-PIO1.19-Pad1)") (class "Default")
      (node (ref "IC2") (pin "1") (pinfunction "PIO1.19_1") (pintype "bidirectional"))
    )
    (net (code "94") (name "unconnected-(JP2-ID-PadID1)") (class "Default")
      (node (ref "JP2") (pin "ID1") (pinfunction "ID_ID1") (pintype "bidirectional"))
    )
    (net (code "95") (name "unconnected-(S2-CENT-PadCTR)") (class "Default")
      (node (ref "S2") (pin "CTR") (pinfunction "CENT_CTR") (pintype "bidirectional"))
    )
    (net (code "96") (name "unconnected-(S2-DOWN-PadD)") (class "Default")
      (node (ref "S2") (pin "D") (pinfunction "DOWN_D") (pintype "bidirectional"))
    )
    (net (code "97") (name "unconnected-(S2-LEFT-PadC)") (class "Default")
      (node (ref "S2") (pin "C") (pinfunction "LEFT_C") (pintype "bidirectional"))
    )
    (net (code "98") (name "unconnected-(S2-RIGHT-PadB)") (class "Default")
      (node (ref "S2") (pin "B") (pinfunction "RIGHT_B") (pintype "bidirectional"))
    )
    (net (code "99") (name "unconnected-(S2-UP-PadA)") (class "Default")
      (node (ref "S2") (pin "A") (pinfunction "UP_A") (pintype "bidirectional"))
    )
    (net (code "100") (name "unconnected-(S3-Pad1)") (class "Default")
      (node (ref "S3") (pin "1") (pinfunction "1_1") (pintype "input"))
    )
    (net (code "101") (name "unconnected-(S3-Pad2)") (class "Default")
      (node (ref "S3") (pin "2") (pinfunction "2_2") (pintype "input"))
    )
    (net (code "102") (name "unconnected-(S3-PadT)") (class "Default")
      (node (ref "S3") (pin "T") (pinfunction "T_T") (pintype "input"))
    )
    (net (code "103") (name "unconnected-(S4-1-Pad4)") (class "Default")
      (node (ref "S4") (pin "4") (pinfunction "1_4") (pintype "passive"))
    )
    (net (code "104") (name "unconnected-(S4-Pad2)") (class "Default")
      (node (ref "S4") (pin "2") (pinfunction "2_2") (pintype "passive"))
    )
    (net (code "105") (name "unconnected-(S4-PadA)") (class "Default")
      (node (ref "S4") (pin "A") (pinfunction "A_A") (pintype "passive"))
    )
    (net (code "106") (name "unconnected-(S4-PadC)") (class "Default")
      (node (ref "S4") (pin "C") (pinfunction "C_C") (pintype "passive"))
    )
    (net (code "107") (name "unconnected-(U1-VCC-Pad4)") (class "Default")
      (node (ref "U1") (pin "4") (pinfunction "VCC_4") (pintype "bidirectional"))
    )
  )
)
